# dpi_rpi.net
KiCad netlist of a schematic drawn in EAGLE
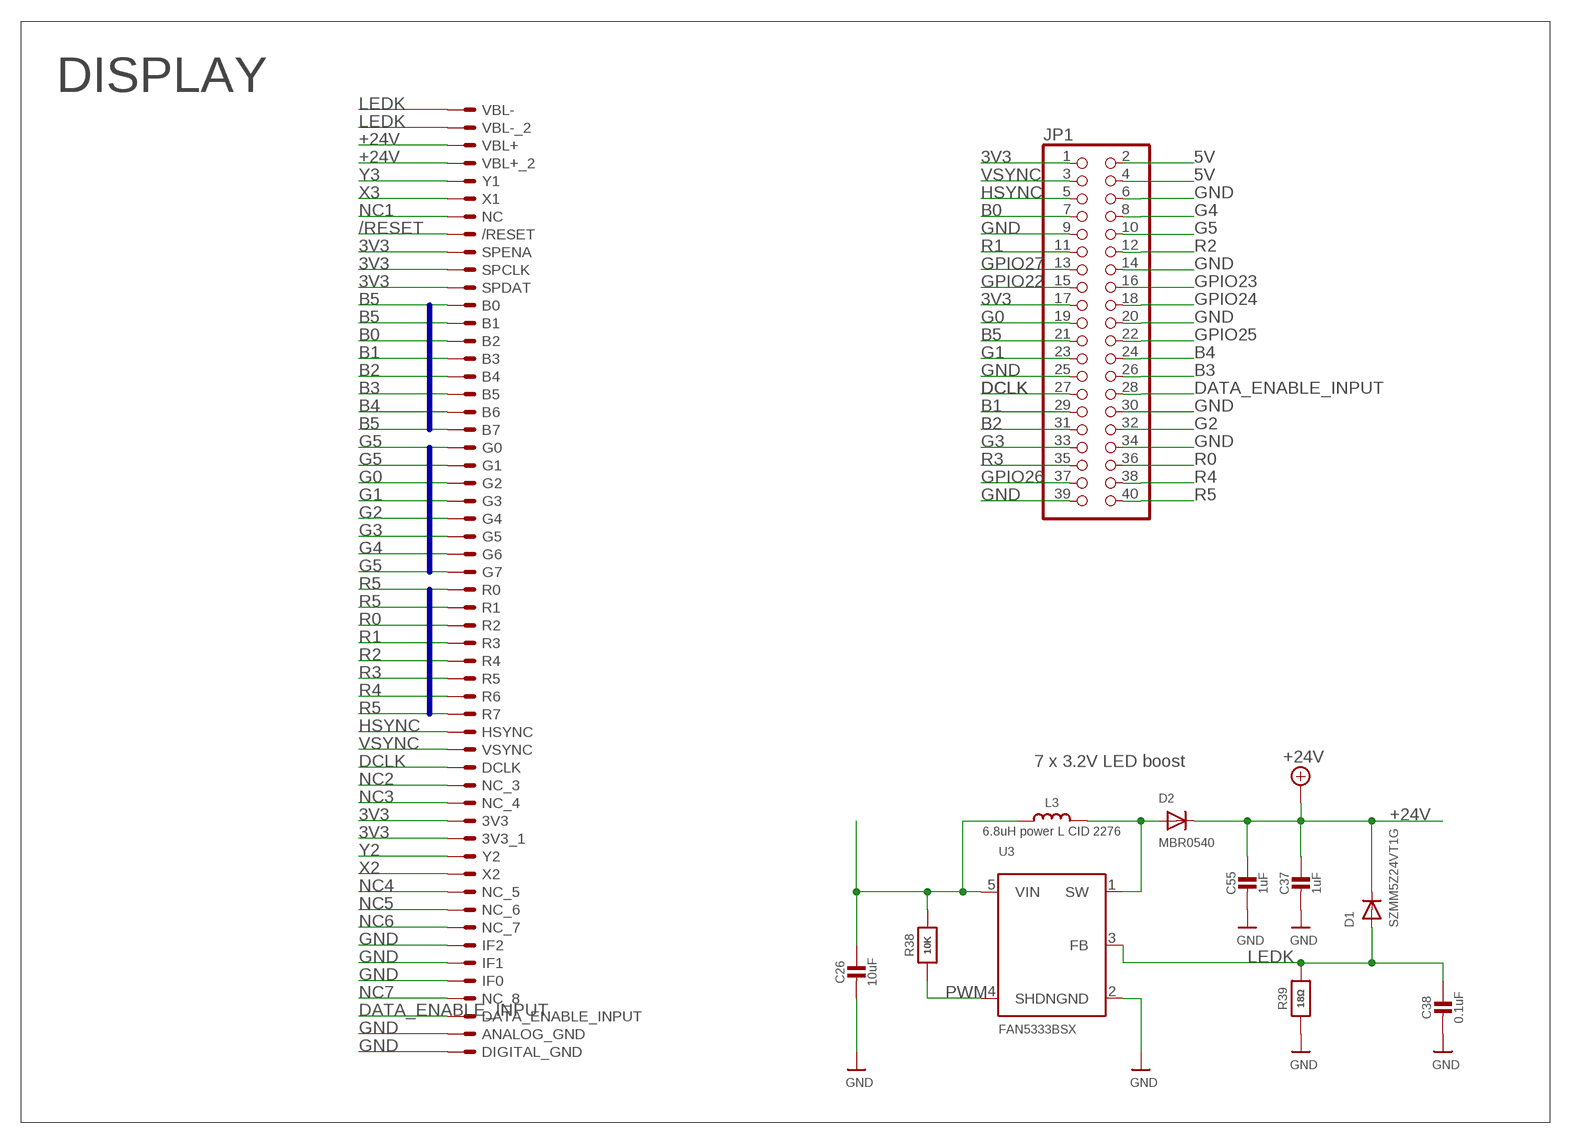
[diagram p0: schematic, sheet 1]

(export (version "E")
  (design (tool "Eeschema 10.0.6"))
  (components
    (comp (ref "C26")
      (value "10uF")
      (footprint "eagle-import:_0805MP")
      (libsource (lib "eagle-import") (part "CAP_CERAMIC_0805MP"))
    )
    (comp (ref "C37")
      (value "1uF")
      (footprint "eagle-import:_0805MP")
      (libsource (lib "eagle-import") (part "CAP_CERAMIC_0805MP"))
    )
    (comp (ref "C38")
      (value "0.1uF")
      (footprint "eagle-import:_0805MP")
      (libsource (lib "eagle-import") (part "CAP_CERAMIC_0805MP"))
    )
    (comp (ref "C55")
      (value "1uF")
      (footprint "eagle-import:_0805MP")
      (libsource (lib "eagle-import") (part "CAP_CERAMIC_0805MP"))
    )
    (comp (ref "D1")
      (value "SZMM5Z24VT1G")
      (footprint "eagle-import:SMADIODE")
      (libsource (lib "eagle-import") (part "DIODESMA"))
    )
    (comp (ref "D2")
      (value "MBR0540")
      (footprint "eagle-import:SOD-123")
      (libsource (lib "eagle-import") (part "DIODESOD-123"))
    )
    (comp (ref "JP1")
      (value "PINHD-2X20")
      (footprint "eagle-import:2X20")
      (libsource (lib "eagle-import") (part "PINHD-2X20"))
    )
    (comp (ref "L3")
      (value "6.8uH power L CID 2276")
      (footprint "eagle-import:INDUCTOR_5X5MM_NR5040_NOTHERMALS")
      (libsource (lib "eagle-import") (part "INDUCTORNR5040"))
    )
    (comp (ref "R38")
      (value "10K")
      (footprint "eagle-import:_0805MP")
      (libsource (lib "eagle-import") (part "RESISTOR_0805MP"))
    )
    (comp (ref "R39")
      (value "18Ω")
      (footprint "eagle-import:_0805MP")
      (libsource (lib "eagle-import") (part "RESISTOR_0805MP"))
    )
    (comp (ref "U$5")
      (value "51296-5494")
      (footprint "eagle-import:51296")
      (fields (field (name "MF") "Molex"))
      (libsource (lib "eagle-import") (part "51296-5494"))
    )
    (comp (ref "U3")
      (value "FAN5333BSX")
      (footprint "eagle-import:SOT23-5@1")
      (libsource (lib "eagle-import") (part "FAN5331"))
    )
  )
  (nets
    (net (code "1") (name "+24V") (class "Default")
      (node (ref "C37") (pin "1") (pinfunction "1_1") (pintype "passive"))
      (node (ref "C55") (pin "1") (pinfunction "1_1") (pintype "passive"))
      (node (ref "D1") (pin "C") (pinfunction "C_C") (pintype "passive"))
      (node (ref "D2") (pin "C") (pinfunction "C_C") (pintype "passive"))
      (node (ref "U$5") (pin "3") (pinfunction "VBL+_3") (pintype "passive"))
      (node (ref "U$5") (pin "4") (pinfunction "VBL+_2_4") (pintype "passive"))
    )
    (net (code "2") (name "/3V3") (class "Default")
      (node (ref "C26") (pin "1") (pinfunction "1_1") (pintype "passive"))
      (node (ref "JP1") (pin "1") (pinfunction "1_1") (pintype "passive"))
      (node (ref "JP1") (pin "17") (pinfunction "17_17") (pintype "passive"))
      (node (ref "L3") (pin "P$1") (pinfunction "1_P$1") (pintype "passive"))
      (node (ref "R38") (pin "2") (pinfunction "2_2") (pintype "passive"))
      (node (ref "U$5") (pin "10") (pinfunction "SPCLK_10") (pintype "passive"))
      (node (ref "U$5") (pin "11") (pinfunction "SPDAT_11") (pintype "passive"))
      (node (ref "U$5") (pin "41") (pinfunction "3V3_41") (pintype "passive"))
      (node (ref "U$5") (pin "42") (pinfunction "3V3_1_42") (pintype "passive"))
      (node (ref "U$5") (pin "9") (pinfunction "SPENA_9") (pintype "passive"))
      (node (ref "U3") (pin "5") (pinfunction "VIN_5") (pintype "bidirectional"))
    )
    (net (code "3") (name "/5V") (class "Default")
      (node (ref "JP1") (pin "2") (pinfunction "2_2") (pintype "passive"))
      (node (ref "JP1") (pin "4") (pinfunction "4_4") (pintype "passive"))
    )
    (net (code "4") (name "/B0") (class "Default")
      (node (ref "JP1") (pin "7") (pinfunction "7_7") (pintype "passive"))
      (node (ref "U$5") (pin "14") (pinfunction "B2_14") (pintype "passive"))
    )
    (net (code "5") (name "/B1") (class "Default")
      (node (ref "JP1") (pin "29") (pinfunction "29_29") (pintype "passive"))
      (node (ref "U$5") (pin "15") (pinfunction "B3_15") (pintype "passive"))
    )
    (net (code "6") (name "/B2") (class "Default")
      (node (ref "JP1") (pin "31") (pinfunction "31_31") (pintype "passive"))
      (node (ref "U$5") (pin "16") (pinfunction "B4_16") (pintype "passive"))
    )
    (net (code "7") (name "/B3") (class "Default")
      (node (ref "JP1") (pin "26") (pinfunction "26_26") (pintype "passive"))
      (node (ref "U$5") (pin "17") (pinfunction "B5_17") (pintype "passive"))
    )
    (net (code "8") (name "/B4") (class "Default")
      (node (ref "JP1") (pin "24") (pinfunction "24_24") (pintype "passive"))
      (node (ref "U$5") (pin "18") (pinfunction "B6_18") (pintype "passive"))
    )
    (net (code "9") (name "/B5") (class "Default")
      (node (ref "JP1") (pin "21") (pinfunction "21_21") (pintype "passive"))
      (node (ref "U$5") (pin "12") (pinfunction "B0_12") (pintype "passive"))
      (node (ref "U$5") (pin "13") (pinfunction "B1_13") (pintype "passive"))
      (node (ref "U$5") (pin "19") (pinfunction "B7_19") (pintype "passive"))
    )
    (net (code "10") (name "/DATA_ENABLE_INPUT") (class "Default")
      (node (ref "JP1") (pin "28") (pinfunction "28_28") (pintype "passive"))
      (node (ref "U$5") (pin "52") (pinfunction "DATA_ENABLE_INPUT_52") (pintype "passive"))
    )
    (net (code "11") (name "/DCLK") (class "Default")
      (node (ref "JP1") (pin "27") (pinfunction "27_27") (pintype "passive"))
      (node (ref "U$5") (pin "38") (pinfunction "DCLK_38") (pintype "passive"))
    )
    (net (code "12") (name "/G0") (class "Default")
      (node (ref "JP1") (pin "19") (pinfunction "19_19") (pintype "passive"))
      (node (ref "U$5") (pin "22") (pinfunction "G2_22") (pintype "passive"))
    )
    (net (code "13") (name "/G1") (class "Default")
      (node (ref "JP1") (pin "23") (pinfunction "23_23") (pintype "passive"))
      (node (ref "U$5") (pin "23") (pinfunction "G3_23") (pintype "passive"))
    )
    (net (code "14") (name "/G2") (class "Default")
      (node (ref "JP1") (pin "32") (pinfunction "32_32") (pintype "passive"))
      (node (ref "U$5") (pin "24") (pinfunction "G4_24") (pintype "passive"))
    )
    (net (code "15") (name "/G3") (class "Default")
      (node (ref "JP1") (pin "33") (pinfunction "33_33") (pintype "passive"))
      (node (ref "U$5") (pin "25") (pinfunction "G5_25") (pintype "passive"))
    )
    (net (code "16") (name "/G4") (class "Default")
      (node (ref "JP1") (pin "8") (pinfunction "8_8") (pintype "passive"))
      (node (ref "U$5") (pin "26") (pinfunction "G6_26") (pintype "passive"))
    )
    (net (code "17") (name "/G5") (class "Default")
      (node (ref "JP1") (pin "10") (pinfunction "10_10") (pintype "passive"))
      (node (ref "U$5") (pin "20") (pinfunction "G0_20") (pintype "passive"))
      (node (ref "U$5") (pin "21") (pinfunction "G1_21") (pintype "passive"))
      (node (ref "U$5") (pin "27") (pinfunction "G7_27") (pintype "passive"))
    )
    (net (code "18") (name "/GPIO22") (class "Default")
      (node (ref "JP1") (pin "15") (pinfunction "15_15") (pintype "passive"))
    )
    (net (code "19") (name "/GPIO23") (class "Default")
      (node (ref "JP1") (pin "16") (pinfunction "16_16") (pintype "passive"))
    )
    (net (code "20") (name "/GPIO24") (class "Default")
      (node (ref "JP1") (pin "18") (pinfunction "18_18") (pintype "passive"))
    )
    (net (code "21") (name "/GPIO25") (class "Default")
      (node (ref "JP1") (pin "22") (pinfunction "22_22") (pintype "passive"))
    )
    (net (code "22") (name "/GPIO26") (class "Default")
      (node (ref "JP1") (pin "37") (pinfunction "37_37") (pintype "passive"))
    )
    (net (code "23") (name "/GPIO27") (class "Default")
      (node (ref "JP1") (pin "13") (pinfunction "13_13") (pintype "passive"))
    )
    (net (code "24") (name "/HSYNC") (class "Default")
      (node (ref "JP1") (pin "5") (pinfunction "5_5") (pintype "passive"))
      (node (ref "U$5") (pin "36") (pinfunction "HSYNC_36") (pintype "passive"))
    )
    (net (code "25") (name "/LEDK") (class "Default")
      (node (ref "C38") (pin "1") (pinfunction "1_1") (pintype "passive"))
      (node (ref "D1") (pin "A") (pinfunction "A_A") (pintype "passive"))
      (node (ref "R39") (pin "2") (pinfunction "2_2") (pintype "passive"))
      (node (ref "U$5") (pin "1") (pinfunction "VBL-_1") (pintype "passive"))
      (node (ref "U$5") (pin "2") (pinfunction "VBL-_2_2") (pintype "passive"))
      (node (ref "U3") (pin "3") (pinfunction "FB_3") (pintype "bidirectional"))
    )
    (net (code "26") (name "/NC1") (class "Default")
      (node (ref "U$5") (pin "7") (pinfunction "NC_7") (pintype "passive"))
    )
    (net (code "27") (name "/NC2") (class "Default")
      (node (ref "U$5") (pin "39") (pinfunction "NC_3_39") (pintype "passive"))
    )
    (net (code "28") (name "/NC3") (class "Default")
      (node (ref "U$5") (pin "40") (pinfunction "NC_4_40") (pintype "passive"))
    )
    (net (code "29") (name "/NC4") (class "Default")
      (node (ref "U$5") (pin "45") (pinfunction "NC_5_45") (pintype "passive"))
    )
    (net (code "30") (name "/NC5") (class "Default")
      (node (ref "U$5") (pin "46") (pinfunction "NC_6_46") (pintype "passive"))
    )
    (net (code "31") (name "/NC6") (class "Default")
      (node (ref "U$5") (pin "47") (pinfunction "NC_7_47") (pintype "passive"))
    )
    (net (code "32") (name "/NC7") (class "Default")
      (node (ref "U$5") (pin "51") (pinfunction "NC_8_51") (pintype "passive"))
    )
    (net (code "33") (name "/PWM") (class "Default")
      (node (ref "R38") (pin "1") (pinfunction "1_1") (pintype "passive"))
      (node (ref "U3") (pin "4") (pinfunction "SHDN_4") (pintype "bidirectional"))
    )
    (net (code "34") (name "/R0") (class "Default")
      (node (ref "JP1") (pin "36") (pinfunction "36_36") (pintype "passive"))
      (node (ref "U$5") (pin "30") (pinfunction "R2_30") (pintype "passive"))
    )
    (net (code "35") (name "/R1") (class "Default")
      (node (ref "JP1") (pin "11") (pinfunction "11_11") (pintype "passive"))
      (node (ref "U$5") (pin "31") (pinfunction "R3_31") (pintype "passive"))
    )
    (net (code "36") (name "/R2") (class "Default")
      (node (ref "JP1") (pin "12") (pinfunction "12_12") (pintype "passive"))
      (node (ref "U$5") (pin "32") (pinfunction "R4_32") (pintype "passive"))
    )
    (net (code "37") (name "/R3") (class "Default")
      (node (ref "JP1") (pin "35") (pinfunction "35_35") (pintype "passive"))
      (node (ref "U$5") (pin "33") (pinfunction "R5_33") (pintype "passive"))
    )
    (net (code "38") (name "/R4") (class "Default")
      (node (ref "JP1") (pin "38") (pinfunction "38_38") (pintype "passive"))
      (node (ref "U$5") (pin "34") (pinfunction "R6_34") (pintype "passive"))
    )
    (net (code "39") (name "/R5") (class "Default")
      (node (ref "JP1") (pin "40") (pinfunction "40_40") (pintype "passive"))
      (node (ref "U$5") (pin "28") (pinfunction "R0_28") (pintype "passive"))
      (node (ref "U$5") (pin "29") (pinfunction "R1_29") (pintype "passive"))
      (node (ref "U$5") (pin "35") (pinfunction "R7_35") (pintype "passive"))
    )
    (net (code "40") (name "/VSYNC") (class "Default")
      (node (ref "JP1") (pin "3") (pinfunction "3_3") (pintype "passive"))
      (node (ref "U$5") (pin "37") (pinfunction "VSYNC_37") (pintype "passive"))
    )
    (net (code "41") (name "/X2") (class "Default")
      (node (ref "U$5") (pin "44") (pinfunction "X2_44") (pintype "passive"))
    )
    (net (code "42") (name "/X3") (class "Default")
      (node (ref "U$5") (pin "6") (pinfunction "X1_6") (pintype "passive"))
    )
    (net (code "43") (name "/Y2") (class "Default")
      (node (ref "U$5") (pin "43") (pinfunction "Y2_43") (pintype "passive"))
    )
    (net (code "44") (name "/Y3") (class "Default")
      (node (ref "U$5") (pin "5") (pinfunction "Y1_5") (pintype "passive"))
    )
    (net (code "45") (name "/{slash}RESET") (class "Default")
      (node (ref "U$5") (pin "8") (pinfunction "/RESET_8") (pintype "passive"))
    )
    (net (code "46") (name "GND") (class "Default")
      (node (ref "C26") (pin "2") (pinfunction "2_2") (pintype "passive"))
      (node (ref "C37") (pin "2") (pinfunction "2_2") (pintype "passive"))
      (node (ref "C38") (pin "2") (pinfunction "2_2") (pintype "passive"))
      (node (ref "C55") (pin "2") (pinfunction "2_2") (pintype "passive"))
      (node (ref "JP1") (pin "14") (pinfunction "14_14") (pintype "passive"))
      (node (ref "JP1") (pin "20") (pinfunction "20_20") (pintype "passive"))
      (node (ref "JP1") (pin "25") (pinfunction "25_25") (pintype "passive"))
      (node (ref "JP1") (pin "30") (pinfunction "30_30") (pintype "passive"))
      (node (ref "JP1") (pin "34") (pinfunction "34_34") (pintype "passive"))
      (node (ref "JP1") (pin "39") (pinfunction "39_39") (pintype "passive"))
      (node (ref "JP1") (pin "6") (pinfunction "6_6") (pintype "passive"))
      (node (ref "JP1") (pin "9") (pinfunction "9_9") (pintype "passive"))
      (node (ref "R39") (pin "1") (pinfunction "1_1") (pintype "passive"))
      (node (ref "U$5") (pin "48") (pinfunction "IF2_48") (pintype "passive"))
      (node (ref "U$5") (pin "49") (pinfunction "IF1_49") (pintype "passive"))
      (node (ref "U$5") (pin "50") (pinfunction "IF0_50") (pintype "passive"))
      (node (ref "U$5") (pin "53") (pinfunction "ANALOG_GND_53") (pintype "passive"))
      (node (ref "U$5") (pin "54") (pinfunction "DIGITAL_GND_54") (pintype "passive"))
      (node (ref "U3") (pin "2") (pinfunction "GND_2") (pintype "bidirectional"))
    )
    (net (code "47") (name "Net-(L3-2)") (class "Default")
      (node (ref "D2") (pin "A") (pinfunction "A_A") (pintype "passive"))
      (node (ref "L3") (pin "P$2") (pinfunction "2_P$2") (pintype "passive"))
      (node (ref "U3") (pin "1") (pinfunction "SW_1") (pintype "bidirectional"))
    )
  )
)
